# x-at-arduino.net
KiCad netlist of a schematic drawn in EAGLE
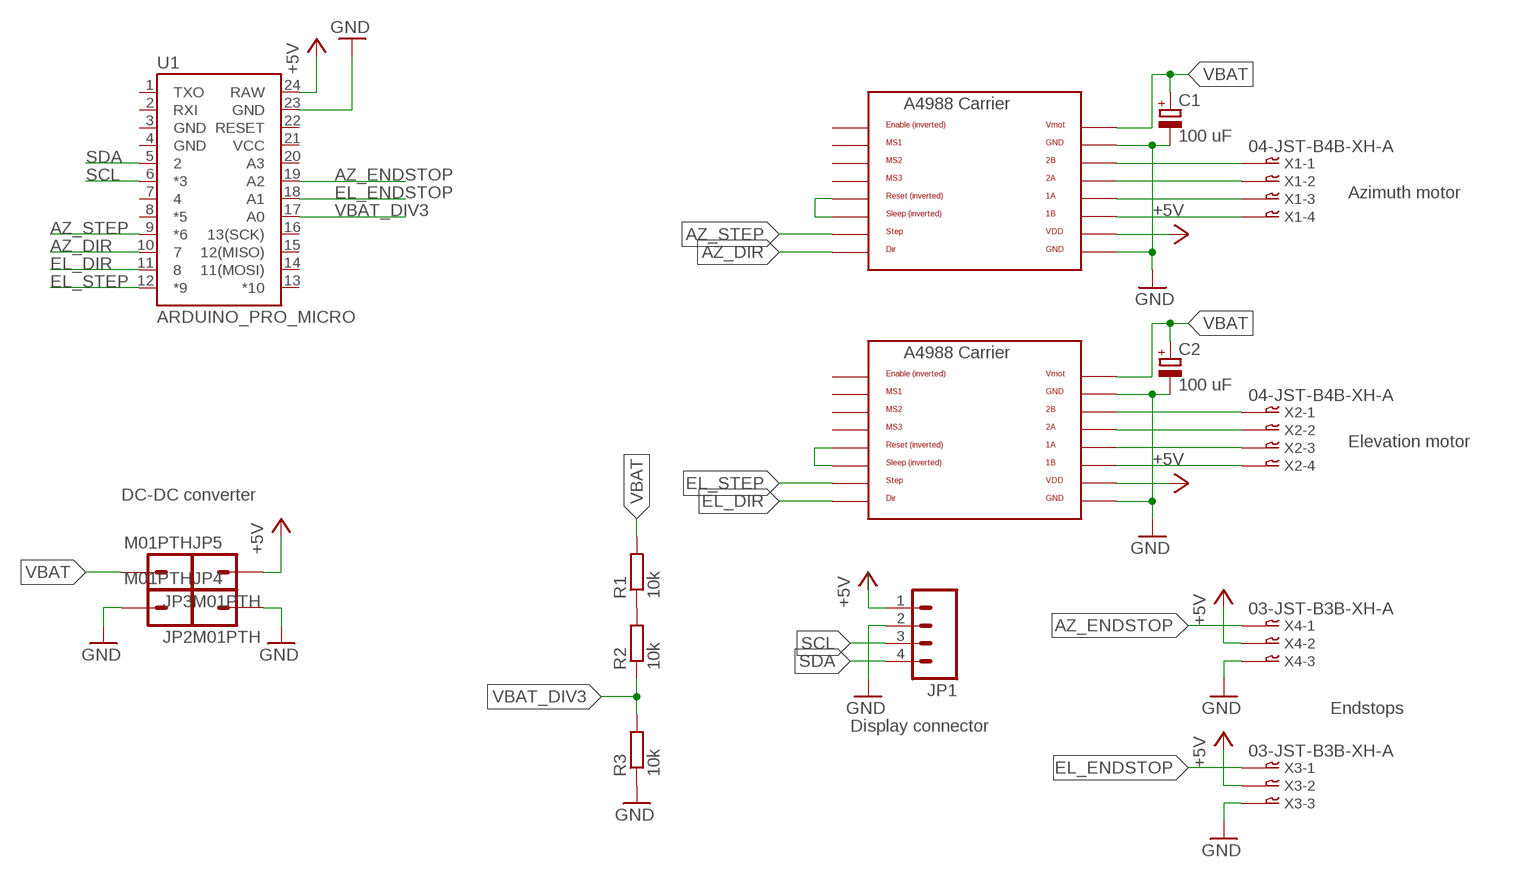
[diagram p0: schematic, sheet 1]

(export (version "E")
  (design (tool "Eeschema 10.0.6"))
  (components
    (comp (ref "C1")
      (value "100 uF")
      (footprint "eagle-import:E5-6")
      (libsource (lib "eagle-import") (part "CPOL-EUE5-6"))
    )
    (comp (ref "C2")
      (value "100 uF")
      (footprint "eagle-import:E5-6")
      (libsource (lib "eagle-import") (part "CPOL-EUE5-6"))
    )
    (comp (ref "JP1")
      (value "M04PTH")
      (footprint "eagle-import:1X04")
      (libsource (lib "eagle-import") (part "M04PTH"))
    )
    (comp (ref "JP2")
      (value "M01PTH")
      (footprint "eagle-import:1X01")
      (libsource (lib "eagle-import") (part "M01PTH"))
    )
    (comp (ref "JP3")
      (value "M01PTH")
      (footprint "eagle-import:1X01")
      (libsource (lib "eagle-import") (part "M01PTH"))
    )
    (comp (ref "JP4")
      (value "M01PTH")
      (footprint "eagle-import:1X01")
      (libsource (lib "eagle-import") (part "M01PTH"))
    )
    (comp (ref "JP5")
      (value "M01PTH")
      (footprint "eagle-import:1X01")
      (libsource (lib "eagle-import") (part "M01PTH"))
    )
    (comp (ref "R1")
      (value "10k")
      (footprint "eagle-import:R0603")
      (libsource (lib "eagle-import") (part "R-EU_R0603"))
    )
    (comp (ref "R2")
      (value "10k")
      (footprint "eagle-import:R0603")
      (libsource (lib "eagle-import") (part "R-EU_R0603"))
    )
    (comp (ref "R3")
      (value "10k")
      (footprint "eagle-import:R0603")
      (libsource (lib "eagle-import") (part "R-EU_R0603"))
    )
    (comp (ref "U1")
      (value "ARDUINO_PRO_MICRO")
      (footprint "eagle-import:ARDUINO_PRO_MICRO")
      (libsource (lib "eagle-import") (part "ARDUINO_PRO_MICRO"))
    )
    (comp (ref "U2")
      (value "POLOLU_A4983CARRIER")
      (footprint "eagle-import:A4988BREAKOUT")
      (libsource (lib "eagle-import") (part "POLOLU_A4983CARRIER"))
    )
    (comp (ref "U3")
      (value "POLOLU_A4983CARRIER")
      (footprint "eagle-import:A4988BREAKOUT")
      (libsource (lib "eagle-import") (part "POLOLU_A4983CARRIER"))
    )
    (comp (ref "X1")
      (value "04-JST-B4B-XH-A")
      (footprint "eagle-import:B4B-XH")
      (libsource (lib "eagle-import") (part "04-JST-B4B-XH-A"))
    )
    (comp (ref "X2")
      (value "04-JST-B4B-XH-A")
      (footprint "eagle-import:B4B-XH")
      (libsource (lib "eagle-import") (part "04-JST-B4B-XH-A"))
    )
    (comp (ref "X3")
      (value "03-JST-B3B-XH-A")
      (footprint "eagle-import:B3B-XH")
      (libsource (lib "eagle-import") (part "03-JST-B3B-XH-A"))
    )
    (comp (ref "X4")
      (value "03-JST-B3B-XH-A")
      (footprint "eagle-import:B3B-XH")
      (libsource (lib "eagle-import") (part "03-JST-B3B-XH-A"))
    )
  )
  (nets
    (net (code "1") (name "+5V") (class "Default")
      (node (ref "JP1") (pin "1") (pinfunction "1_1") (pintype "passive"))
      (node (ref "JP5") (pin "1") (pinfunction "1_1") (pintype "passive"))
      (node (ref "U1") (pin "24") (pinfunction "RAW_24") (pintype "bidirectional"))
      (node (ref "U2") (pin "VDD") (pinfunction "VDD_VDD") (pintype "power_in"))
      (node (ref "U3") (pin "VDD") (pinfunction "VDD_VDD") (pintype "power_in"))
      (node (ref "X3") (pin "P$2") (pinfunction "1_P$2") (pintype "passive"))
      (node (ref "X4") (pin "P$2") (pinfunction "1_P$2") (pintype "passive"))
    )
    (net (code "2") (name "AZ_DIR") (class "Default")
      (node (ref "U1") (pin "10") (pinfunction "7_10") (pintype "bidirectional"))
      (node (ref "U2") (pin "DIR") (pinfunction "DIR_DIR") (pintype "input"))
    )
    (net (code "3") (name "AZ_ENDSTOP") (class "Default")
      (node (ref "U1") (pin "19") (pinfunction "A2_19") (pintype "bidirectional"))
      (node (ref "X4") (pin "P$1") (pinfunction "1_P$1") (pintype "passive"))
    )
    (net (code "4") (name "AZ_STEP") (class "Default")
      (node (ref "U1") (pin "9") (pinfunction "*6_9") (pintype "bidirectional"))
      (node (ref "U2") (pin "STEP") (pinfunction "STEP_STEP") (pintype "input"))
    )
    (net (code "5") (name "EL_DIR") (class "Default")
      (node (ref "U1") (pin "11") (pinfunction "8_11") (pintype "bidirectional"))
      (node (ref "U3") (pin "DIR") (pinfunction "DIR_DIR") (pintype "input"))
    )
    (net (code "6") (name "EL_ENDSTOP") (class "Default")
      (node (ref "U1") (pin "18") (pinfunction "A1_18") (pintype "bidirectional"))
      (node (ref "X3") (pin "P$1") (pinfunction "1_P$1") (pintype "passive"))
    )
    (net (code "7") (name "EL_STEP") (class "Default")
      (node (ref "U1") (pin "12") (pinfunction "*9_12") (pintype "bidirectional"))
      (node (ref "U3") (pin "STEP") (pinfunction "STEP_STEP") (pintype "input"))
    )
    (net (code "8") (name "GND") (class "Default")
      (node (ref "C1") (pin "-") (pinfunction "-_-") (pintype "passive"))
      (node (ref "C2") (pin "-") (pinfunction "-_-") (pintype "passive"))
      (node (ref "JP1") (pin "2") (pinfunction "2_2") (pintype "passive"))
      (node (ref "JP2") (pin "1") (pinfunction "1_1") (pintype "passive"))
      (node (ref "JP4") (pin "1") (pinfunction "1_1") (pintype "passive"))
      (node (ref "R3") (pin "1") (pinfunction "1_1") (pintype "passive"))
      (node (ref "U1") (pin "23") (pinfunction "GND_23") (pintype "bidirectional"))
      (node (ref "U2") (pin "GND") (pinfunction "GND_GND") (pintype "power_in"))
      (node (ref "U2") (pin "GND@0") (pinfunction "GND_GND@0") (pintype "power_in"))
      (node (ref "U3") (pin "GND") (pinfunction "GND_GND") (pintype "power_in"))
      (node (ref "U3") (pin "GND@0") (pinfunction "GND_GND@0") (pintype "power_in"))
      (node (ref "X3") (pin "P$3") (pinfunction "1_P$3") (pintype "passive"))
      (node (ref "X4") (pin "P$3") (pinfunction "1_P$3") (pintype "passive"))
    )
    (net (code "9") (name "Net-(R1-Pad1)") (class "Default")
      (node (ref "R1") (pin "1") (pinfunction "1_1") (pintype "passive"))
      (node (ref "R2") (pin "2") (pinfunction "2_2") (pintype "passive"))
    )
    (net (code "10") (name "Net-(U2-SLEEP)") (class "Default")
      (node (ref "U2") (pin "RST") (pinfunction "RST_RST") (pintype "input"))
      (node (ref "U2") (pin "SLP") (pinfunction "SLEEP_SLP") (pintype "input"))
    )
    (net (code "11") (name "Net-(U3-SLEEP)") (class "Default")
      (node (ref "U3") (pin "RST") (pinfunction "RST_RST") (pintype "input"))
      (node (ref "U3") (pin "SLP") (pinfunction "SLEEP_SLP") (pintype "input"))
    )
    (net (code "12") (name "Net-(X1A-1)") (class "Default")
      (node (ref "U2") (pin "2B") (pinfunction "2B_2B") (pintype "output"))
      (node (ref "X1") (pin "P$1") (pinfunction "1_P$1") (pintype "passive"))
    )
    (net (code "13") (name "Net-(X1B-1)") (class "Default")
      (node (ref "U2") (pin "2A") (pinfunction "2A_2A") (pintype "output"))
      (node (ref "X1") (pin "P$2") (pinfunction "1_P$2") (pintype "passive"))
    )
    (net (code "14") (name "Net-(X1C-1)") (class "Default")
      (node (ref "U2") (pin "1A") (pinfunction "1A_1A") (pintype "output"))
      (node (ref "X1") (pin "P$3") (pinfunction "1_P$3") (pintype "passive"))
    )
    (net (code "15") (name "Net-(X1D-1)") (class "Default")
      (node (ref "U2") (pin "1B") (pinfunction "1B_1B") (pintype "output"))
      (node (ref "X1") (pin "P$4") (pinfunction "1_P$4") (pintype "passive"))
    )
    (net (code "16") (name "Net-(X2A-1)") (class "Default")
      (node (ref "U3") (pin "2B") (pinfunction "2B_2B") (pintype "output"))
      (node (ref "X2") (pin "P$1") (pinfunction "1_P$1") (pintype "passive"))
    )
    (net (code "17") (name "Net-(X2B-1)") (class "Default")
      (node (ref "U3") (pin "2A") (pinfunction "2A_2A") (pintype "output"))
      (node (ref "X2") (pin "P$2") (pinfunction "1_P$2") (pintype "passive"))
    )
    (net (code "18") (name "Net-(X2C-1)") (class "Default")
      (node (ref "U3") (pin "1A") (pinfunction "1A_1A") (pintype "output"))
      (node (ref "X2") (pin "P$3") (pinfunction "1_P$3") (pintype "passive"))
    )
    (net (code "19") (name "Net-(X2D-1)") (class "Default")
      (node (ref "U3") (pin "1B") (pinfunction "1B_1B") (pintype "output"))
      (node (ref "X2") (pin "P$4") (pinfunction "1_P$4") (pintype "passive"))
    )
    (net (code "20") (name "SCL") (class "Default")
      (node (ref "JP1") (pin "3") (pinfunction "3_3") (pintype "passive"))
      (node (ref "U1") (pin "6") (pinfunction "*3_6") (pintype "bidirectional"))
    )
    (net (code "21") (name "SDA") (class "Default")
      (node (ref "JP1") (pin "4") (pinfunction "4_4") (pintype "passive"))
      (node (ref "U1") (pin "5") (pinfunction "2_5") (pintype "bidirectional"))
    )
    (net (code "22") (name "VBAT") (class "Default")
      (node (ref "C1") (pin "+") (pinfunction "+_+") (pintype "passive"))
      (node (ref "C2") (pin "+") (pinfunction "+_+") (pintype "passive"))
      (node (ref "JP3") (pin "1") (pinfunction "1_1") (pintype "passive"))
      (node (ref "R1") (pin "2") (pinfunction "2_2") (pintype "passive"))
      (node (ref "U2") (pin "VMOT") (pinfunction "VMOT_VMOT") (pintype "power_in"))
      (node (ref "U3") (pin "VMOT") (pinfunction "VMOT_VMOT") (pintype "power_in"))
    )
    (net (code "23") (name "VBAT_DIV3") (class "Default")
      (node (ref "R2") (pin "1") (pinfunction "1_1") (pintype "passive"))
      (node (ref "R3") (pin "2") (pinfunction "2_2") (pintype "passive"))
      (node (ref "U1") (pin "17") (pinfunction "A0_17") (pintype "bidirectional"))
    )
    (net (code "24") (name "unconnected-(U1-*5-Pad8)") (class "Default")
      (node (ref "U1") (pin "8") (pinfunction "*5_8") (pintype "bidirectional"))
    )
    (net (code "25") (name "unconnected-(U1-*10-Pad13)") (class "Default")
      (node (ref "U1") (pin "13") (pinfunction "*10_13") (pintype "bidirectional"))
    )
    (net (code "26") (name "unconnected-(U1-4-Pad7)") (class "Default")
      (node (ref "U1") (pin "7") (pinfunction "4_7") (pintype "bidirectional"))
    )
    (net (code "27") (name "unconnected-(U1-11(MOSI)-Pad14)") (class "Default")
      (node (ref "U1") (pin "14") (pinfunction "11(MOSI)_14") (pintype "bidirectional"))
    )
    (net (code "28") (name "unconnected-(U1-12(MISO)-Pad15)") (class "Default")
      (node (ref "U1") (pin "15") (pinfunction "12(MISO)_15") (pintype "bidirectional"))
    )
    (net (code "29") (name "unconnected-(U1-13(SCK)-Pad16)") (class "Default")
      (node (ref "U1") (pin "16") (pinfunction "13(SCK)_16") (pintype "bidirectional"))
    )
    (net (code "30") (name "unconnected-(U1-A3-Pad20)") (class "Default")
      (node (ref "U1") (pin "20") (pinfunction "A3_20") (pintype "bidirectional"))
    )
    (net (code "31") (name "unconnected-(U1-GND-Pad3)") (class "Default")
      (node (ref "U1") (pin "3") (pinfunction "GND_3") (pintype "bidirectional"))
    )
    (net (code "32") (name "unconnected-(U1-GND-Pad4)") (class "Default")
      (node (ref "U1") (pin "4") (pinfunction "GND_4") (pintype "bidirectional"))
    )
    (net (code "33") (name "unconnected-(U1-RESET-Pad22)") (class "Default")
      (node (ref "U1") (pin "22") (pinfunction "RESET_22") (pintype "bidirectional"))
    )
    (net (code "34") (name "unconnected-(U1-RXI-Pad2)") (class "Default")
      (node (ref "U1") (pin "2") (pinfunction "RXI_2") (pintype "bidirectional"))
    )
    (net (code "35") (name "unconnected-(U1-TXO-Pad1)") (class "Default")
      (node (ref "U1") (pin "1") (pinfunction "TXO_1") (pintype "bidirectional"))
    )
    (net (code "36") (name "unconnected-(U1-VCC-Pad21)") (class "Default")
      (node (ref "U1") (pin "21") (pinfunction "VCC_21") (pintype "bidirectional"))
    )
    (net (code "37") (name "unconnected-(U2-PadEN)") (class "Default")
      (node (ref "U2") (pin "EN") (pinfunction "EN_EN") (pintype "input"))
    )
    (net (code "38") (name "unconnected-(U2-PadMS1)") (class "Default")
      (node (ref "U2") (pin "MS1") (pinfunction "MS1_MS1") (pintype "input"))
    )
    (net (code "39") (name "unconnected-(U2-PadMS2)") (class "Default")
      (node (ref "U2") (pin "MS2") (pinfunction "MS2_MS2") (pintype "input"))
    )
    (net (code "40") (name "unconnected-(U2-PadMS3)") (class "Default")
      (node (ref "U2") (pin "MS3") (pinfunction "MS3_MS3") (pintype "input"))
    )
    (net (code "41") (name "unconnected-(U3-PadEN)") (class "Default")
      (node (ref "U3") (pin "EN") (pinfunction "EN_EN") (pintype "input"))
    )
    (net (code "42") (name "unconnected-(U3-PadMS1)") (class "Default")
      (node (ref "U3") (pin "MS1") (pinfunction "MS1_MS1") (pintype "input"))
    )
    (net (code "43") (name "unconnected-(U3-PadMS2)") (class "Default")
      (node (ref "U3") (pin "MS2") (pinfunction "MS2_MS2") (pintype "input"))
    )
    (net (code "44") (name "unconnected-(U3-PadMS3)") (class "Default")
      (node (ref "U3") (pin "MS3") (pinfunction "MS3_MS3") (pintype "input"))
    )
  )
)
